# MotorSheet.net
KiCad netlist of a schematic drawn in Altium Designer
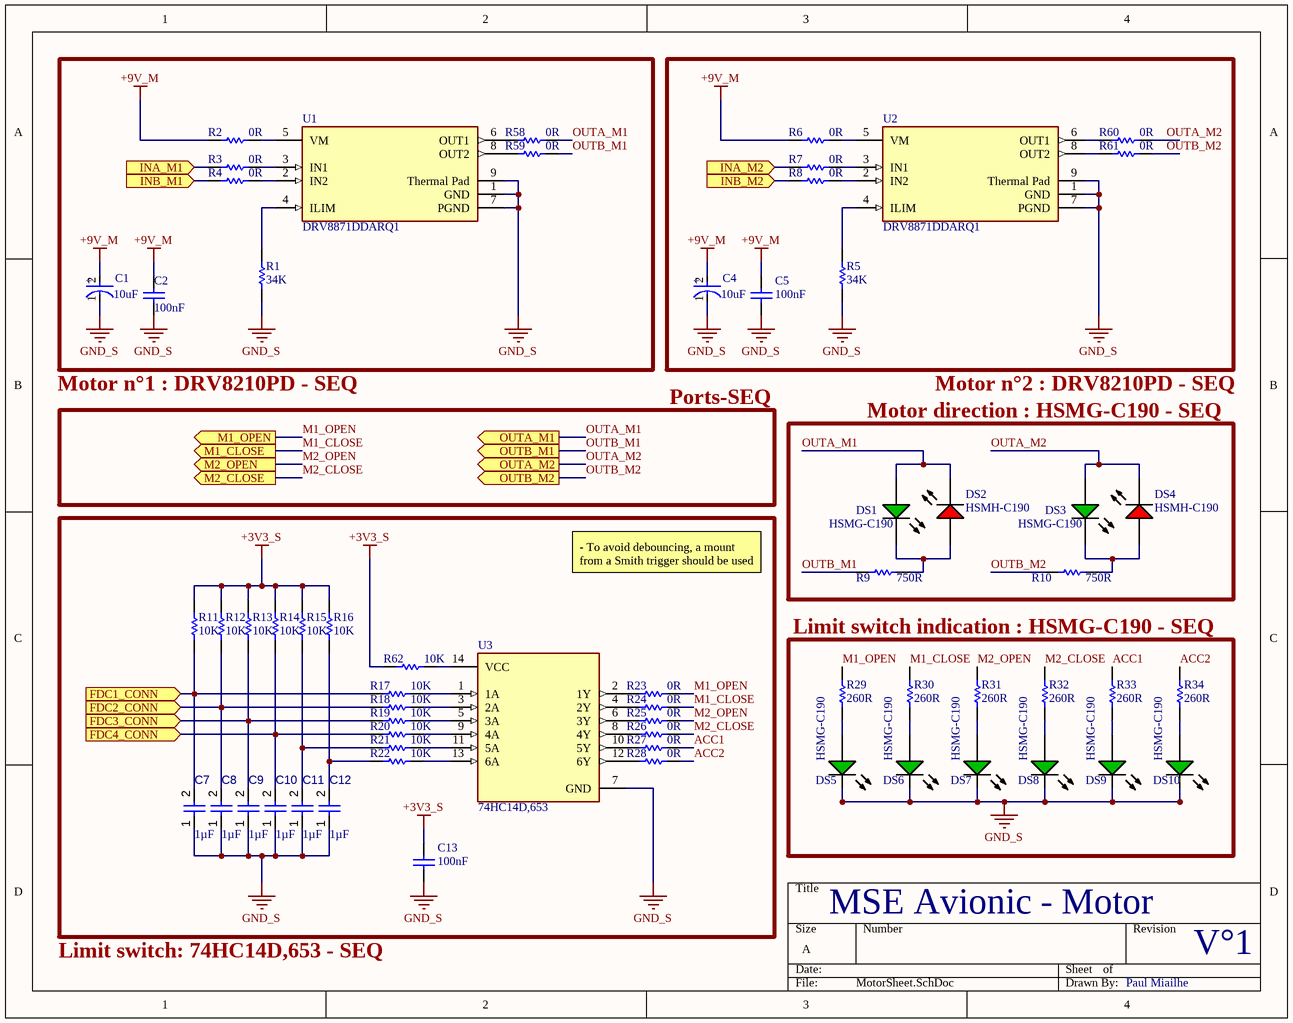
[diagram p0: MotorSheet.SchDoc]

(export (version "E")
  (design (tool "Eeschema 10.0.6"))
  (components
    (comp (ref "C1")
      (value "EEE1VA100SR")
      (footprint "FP-SC-MFG")
      (description "CAP ALUM 10UF 20% 35V SMD")
      (fields
        (field (name "CAPACITANCE") "10uF")
        (field (name "TOLERANCE") "20%")
        (field (name "VOLTAGE") "35V")
      )
      (libsource (lib "Altium Content Vault") (part "203bc49f2ac43e59fd269a8c329ed05"))
    )
    (comp (ref "C2")
      (value "GRM21BR71H104KA01L")
      (footprint "CAPC2013X135X45ML10T25")
      (description "Chip Capacitor, 0.1 uF, +/- 10%, 50 V, -55 to 125 degC, 0805 (2012 Metric), RoHS, Tape and Reel")
      (fields
        (field (name "VOLTAGE") "50V")
        (field (name "CAPACITANCE") "100nF")
        (field (name "TOLERANCE") "10%")
      )
      (libsource (lib "Altium Content Vault") (part "CAP-NP-2"))
    )
    (comp (ref "C4")
      (value "EEE1VA100SR")
      (footprint "FP-SC-MFG")
      (description "CAP ALUM 10UF 20% 35V SMD")
      (fields
        (field (name "CAPACITANCE") "10uF")
        (field (name "TOLERANCE") "20%")
        (field (name "VOLTAGE") "35V")
      )
      (libsource (lib "Altium Content Vault") (part "203bc49f2ac43e59fd269a8c329ed05"))
    )
    (comp (ref "C5")
      (value "GRM21BR71H104KA01L")
      (footprint "CAPC2013X135X45ML10T25")
      (description "Chip Capacitor, 0.1 uF, +/- 10%, 50 V, -55 to 125 degC, 0805 (2012 Metric), RoHS, Tape and Reel")
      (fields
        (field (name "VOLTAGE") "50V")
        (field (name "CAPACITANCE") "100nF")
        (field (name "TOLERANCE") "10%")
      )
      (libsource (lib "Altium Content Vault") (part "CAP-NP-2"))
    )
    (comp (ref "C7")
      (value "1µF")
      (footprint "CAPC0603(1608)100_L")
      (description "Chip Capacitor, 1µF +/-0.1%, 25V, 0603, Thickness 1 mm")
      (fields (field (name "TOLERANCE") "20%") (field (name "Comment") "Capacitor 1µF +/-0.1% 25V 0603"))
      (libsource (lib "Saint-Étienne School of Mines- Mines Space") (part "CAP-NP-2"))
    )
    (comp (ref "C8")
      (value "1µF")
      (footprint "CAPC0603(1608)100_L")
      (description "Chip Capacitor, 1µF +/-0.1%, 25V, 0603, Thickness 1 mm")
      (fields (field (name "TOLERANCE") "20%") (field (name "Comment") "Capacitor 1µF +/-0.1% 25V 0603"))
      (libsource (lib "Saint-Étienne School of Mines- Mines Space") (part "CAP-NP-2"))
    )
    (comp (ref "C9")
      (value "1µF")
      (footprint "CAPC0603(1608)100_L")
      (description "Chip Capacitor, 1µF +/-0.1%, 25V, 0603, Thickness 1 mm")
      (fields (field (name "TOLERANCE") "20%") (field (name "Comment") "Capacitor 1µF +/-0.1% 25V 0603"))
      (libsource (lib "Saint-Étienne School of Mines- Mines Space") (part "CAP-NP-2"))
    )
    (comp (ref "C10")
      (value "1µF")
      (footprint "CAPC0603(1608)100_L")
      (description "Chip Capacitor, 1µF +/-0.1%, 25V, 0603, Thickness 1 mm")
      (fields (field (name "TOLERANCE") "20%") (field (name "Comment") "Capacitor 1µF +/-0.1% 25V 0603"))
      (libsource (lib "Saint-Étienne School of Mines- Mines Space") (part "CAP-NP-2"))
    )
    (comp (ref "C11")
      (value "1µF")
      (footprint "CAPC0603(1608)100_L")
      (description "Chip Capacitor, 1µF +/-0.1%, 25V, 0603, Thickness 1 mm")
      (fields (field (name "TOLERANCE") "20%") (field (name "Comment") "Capacitor 1µF +/-0.1% 25V 0603"))
      (libsource (lib "Saint-Étienne School of Mines- Mines Space") (part "CAP-NP-2"))
    )
    (comp (ref "C12")
      (value "1µF")
      (footprint "CAPC0603(1608)100_L")
      (description "Chip Capacitor, 1µF +/-0.1%, 25V, 0603, Thickness 1 mm")
      (fields (field (name "TOLERANCE") "20%") (field (name "Comment") "Capacitor 1µF +/-0.1% 25V 0603"))
      (libsource (lib "Saint-Étienne School of Mines- Mines Space") (part "CAP-NP-2"))
    )
    (comp (ref "C13")
      (value "GRM21BR71H104KA01L")
      (footprint "CAPC2013X135X45ML10T25")
      (description "Chip Capacitor, 0.1 uF, +/- 10%, 50 V, -55 to 125 degC, 0805 (2012 Metric), RoHS, Tape and Reel")
      (fields
        (field (name "VOLTAGE") "50V")
        (field (name "CAPACITANCE") "100nF")
        (field (name "TOLERANCE") "10%")
      )
      (libsource (lib "Altium Content Vault") (part "CAP-NP-2"))
    )
    (comp (ref "DS1")
      (value "HSMG-C190")
      (footprint "AVAG-HSMX-C190_V")
      (description "Chip LED, Green, 2.2 V, -40 to 85 degC, 2-Pin SMD, RoHS, Tape and Reel")
      (libsource (lib "Altium Content Vault") (part "LED-GREEN-AK-2"))
    )
    (comp (ref "DS2")
      (value "HSMH-C190")
      (footprint "AVAG-HSMX-C190_V")
      (description "LED Uni-Color Red, 65 mW, 20 mA, -40 to 85 degC, 2-Pin SMD, RoHS, Tape and Reel")
      (libsource (lib "Altium Content Vault") (part "LED-RED-AK-2"))
    )
    (comp (ref "DS3")
      (value "HSMG-C190")
      (footprint "AVAG-HSMX-C190_V")
      (description "Chip LED, Green, 2.2 V, -40 to 85 degC, 2-Pin SMD, RoHS, Tape and Reel")
      (libsource (lib "Altium Content Vault") (part "LED-GREEN-AK-2"))
    )
    (comp (ref "DS4")
      (value "HSMH-C190")
      (footprint "AVAG-HSMX-C190_V")
      (description "LED Uni-Color Red, 65 mW, 20 mA, -40 to 85 degC, 2-Pin SMD, RoHS, Tape and Reel")
      (libsource (lib "Altium Content Vault") (part "LED-RED-AK-2"))
    )
    (comp (ref "DS5")
      (value "HSMG-C190")
      (footprint "AVAG-HSMX-C190_V")
      (description "Chip LED, Green, 2.2 V, -40 to 85 degC, 2-Pin SMD, RoHS, Tape and Reel")
      (libsource (lib "Altium Content Vault") (part "LED-GREEN-AK-2"))
    )
    (comp (ref "DS6")
      (value "HSMG-C190")
      (footprint "AVAG-HSMX-C190_V")
      (description "Chip LED, Green, 2.2 V, -40 to 85 degC, 2-Pin SMD, RoHS, Tape and Reel")
      (libsource (lib "Altium Content Vault") (part "LED-GREEN-AK-2"))
    )
    (comp (ref "DS7")
      (value "HSMG-C190")
      (footprint "AVAG-HSMX-C190_V")
      (description "Chip LED, Green, 2.2 V, -40 to 85 degC, 2-Pin SMD, RoHS, Tape and Reel")
      (libsource (lib "Altium Content Vault") (part "LED-GREEN-AK-2"))
    )
    (comp (ref "DS8")
      (value "HSMG-C190")
      (footprint "AVAG-HSMX-C190_V")
      (description "Chip LED, Green, 2.2 V, -40 to 85 degC, 2-Pin SMD, RoHS, Tape and Reel")
      (libsource (lib "Altium Content Vault") (part "LED-GREEN-AK-2"))
    )
    (comp (ref "DS9")
      (value "HSMG-C190")
      (footprint "AVAG-HSMX-C190_V")
      (description "Chip LED, Green, 2.2 V, -40 to 85 degC, 2-Pin SMD, RoHS, Tape and Reel")
      (libsource (lib "Altium Content Vault") (part "LED-GREEN-AK-2"))
    )
    (comp (ref "DS10")
      (value "HSMG-C190")
      (footprint "AVAG-HSMX-C190_V")
      (description "Chip LED, Green, 2.2 V, -40 to 85 degC, 2-Pin SMD, RoHS, Tape and Reel")
      (libsource (lib "Altium Content Vault") (part "LED-GREEN-AK-2"))
    )
    (comp (ref "R1")
      (value "RC0603JR-070RL")
      (footprint "RESC1608X55X25ML10T15")
      (description "Chip Resistor, 0 Ohm, +/- 5%, 0.1 W, -55 to 155 degC, 0603 (1608 Metric), RoHS, Tape and Reel")
      (fields
        (field (name "TOLERANCE") "5%")
        (field (name "RESISTANCE") "34K")
        (field (name "MANUFACTURER") "Yageo")
      )
      (libsource (lib "Altium Content Vault") (part "RES-2"))
    )
    (comp (ref "R2")
      (value "RC0603JR-070RL")
      (footprint "RESC1608X55X25ML10T15")
      (description "Chip Resistor, 0 Ohm, +/- 5%, 0.1 W, -55 to 155 degC, 0603 (1608 Metric), RoHS, Tape and Reel")
      (fields
        (field (name "TOLERANCE") "5%")
        (field (name "RESISTANCE") "0R")
        (field (name "MANUFACTURER") "Yageo")
      )
      (libsource (lib "Altium Content Vault") (part "RES-2"))
    )
    (comp (ref "R3")
      (value "RC0603JR-070RL")
      (footprint "RESC1608X55X25ML10T15")
      (description "Chip Resistor, 0 Ohm, +/- 5%, 0.1 W, -55 to 155 degC, 0603 (1608 Metric), RoHS, Tape and Reel")
      (fields
        (field (name "TOLERANCE") "5%")
        (field (name "RESISTANCE") "0R")
        (field (name "MANUFACTURER") "Yageo")
      )
      (libsource (lib "Altium Content Vault") (part "RES-2"))
    )
    (comp (ref "R4")
      (value "RC0603JR-070RL")
      (footprint "RESC1608X55X25ML10T15")
      (description "Chip Resistor, 0 Ohm, +/- 5%, 0.1 W, -55 to 155 degC, 0603 (1608 Metric), RoHS, Tape and Reel")
      (fields
        (field (name "TOLERANCE") "5%")
        (field (name "RESISTANCE") "0R")
        (field (name "MANUFACTURER") "Yageo")
      )
      (libsource (lib "Altium Content Vault") (part "RES-2"))
    )
    (comp (ref "R5")
      (value "RC0603JR-070RL")
      (footprint "RESC1608X55X25ML10T15")
      (description "Chip Resistor, 0 Ohm, +/- 5%, 0.1 W, -55 to 155 degC, 0603 (1608 Metric), RoHS, Tape and Reel")
      (fields
        (field (name "TOLERANCE") "5%")
        (field (name "RESISTANCE") "34K")
        (field (name "MANUFACTURER") "Yageo")
      )
      (libsource (lib "Altium Content Vault") (part "RES-2"))
    )
    (comp (ref "R6")
      (value "RC0603JR-070RL")
      (footprint "RESC1608X55X25ML10T15")
      (description "Chip Resistor, 0 Ohm, +/- 5%, 0.1 W, -55 to 155 degC, 0603 (1608 Metric), RoHS, Tape and Reel")
      (fields
        (field (name "TOLERANCE") "5%")
        (field (name "RESISTANCE") "0R")
        (field (name "MANUFACTURER") "Yageo")
      )
      (libsource (lib "Altium Content Vault") (part "RES-2"))
    )
    (comp (ref "R7")
      (value "RC0603JR-070RL")
      (footprint "RESC1608X55X25ML10T15")
      (description "Chip Resistor, 0 Ohm, +/- 5%, 0.1 W, -55 to 155 degC, 0603 (1608 Metric), RoHS, Tape and Reel")
      (fields
        (field (name "TOLERANCE") "5%")
        (field (name "RESISTANCE") "0R")
        (field (name "MANUFACTURER") "Yageo")
      )
      (libsource (lib "Altium Content Vault") (part "RES-2"))
    )
    (comp (ref "R8")
      (value "RC0603JR-070RL")
      (footprint "RESC1608X55X25ML10T15")
      (description "Chip Resistor, 0 Ohm, +/- 5%, 0.1 W, -55 to 155 degC, 0603 (1608 Metric), RoHS, Tape and Reel")
      (fields
        (field (name "TOLERANCE") "5%")
        (field (name "RESISTANCE") "0R")
        (field (name "MANUFACTURER") "Yageo")
      )
      (libsource (lib "Altium Content Vault") (part "RES-2"))
    )
    (comp (ref "R9")
      (value "ERA-3AEB751V")
      (footprint "RESC1608X55X30ML20T20")
      (fields
        (field (name "MANUFACTURER") "Panasonic")
        (field (name "TOLERANCE") "0.1%")
        (field (name "RESISTANCE") "750R")
      )
      (libsource (lib "Altium Content Vault") (part "RES"))
    )
    (comp (ref "R10")
      (value "ERA-3AEB751V")
      (footprint "RESC1608X55X30ML20T20")
      (fields
        (field (name "MANUFACTURER") "Panasonic")
        (field (name "TOLERANCE") "0.1%")
        (field (name "RESISTANCE") "750R")
      )
      (libsource (lib "Altium Content Vault") (part "RES"))
    )
    (comp (ref "R11")
      (value "ERJ3EKF1002V")
      (footprint "RESC1609X55X30LL15T15")
      (description "Chip Resistor, 10 KOhm, +/- 1%, 0.1 W, -55 to 155 degC, 0603 (1608 Metric), RoHS, Tape and Reel")
      (fields
        (field (name "RESISTANCE") "10K")
        (field (name "TOLERANCE") "1%")
        (field (name "MANUFACTURER") "Panasonic")
      )
      (libsource (lib "Altium Content Vault") (part "RES-2"))
    )
    (comp (ref "R12")
      (value "ERJ3EKF1002V")
      (footprint "RESC1609X55X30LL15T15")
      (description "Chip Resistor, 10 KOhm, +/- 1%, 0.1 W, -55 to 155 degC, 0603 (1608 Metric), RoHS, Tape and Reel")
      (fields
        (field (name "RESISTANCE") "10K")
        (field (name "TOLERANCE") "1%")
        (field (name "MANUFACTURER") "Panasonic")
      )
      (libsource (lib "Altium Content Vault") (part "RES-2"))
    )
    (comp (ref "R13")
      (value "ERJ3EKF1002V")
      (footprint "RESC1609X55X30LL15T15")
      (description "Chip Resistor, 10 KOhm, +/- 1%, 0.1 W, -55 to 155 degC, 0603 (1608 Metric), RoHS, Tape and Reel")
      (fields
        (field (name "RESISTANCE") "10K")
        (field (name "TOLERANCE") "1%")
        (field (name "MANUFACTURER") "Panasonic")
      )
      (libsource (lib "Altium Content Vault") (part "RES-2"))
    )
    (comp (ref "R14")
      (value "ERJ3EKF1002V")
      (footprint "RESC1609X55X30LL15T15")
      (description "Chip Resistor, 10 KOhm, +/- 1%, 0.1 W, -55 to 155 degC, 0603 (1608 Metric), RoHS, Tape and Reel")
      (fields
        (field (name "RESISTANCE") "10K")
        (field (name "TOLERANCE") "1%")
        (field (name "MANUFACTURER") "Panasonic")
      )
      (libsource (lib "Altium Content Vault") (part "RES-2"))
    )
    (comp (ref "R15")
      (value "ERJ3EKF1002V")
      (footprint "RESC1609X55X30LL15T15")
      (description "Chip Resistor, 10 KOhm, +/- 1%, 0.1 W, -55 to 155 degC, 0603 (1608 Metric), RoHS, Tape and Reel")
      (fields
        (field (name "RESISTANCE") "10K")
        (field (name "TOLERANCE") "1%")
        (field (name "MANUFACTURER") "Panasonic")
      )
      (libsource (lib "Altium Content Vault") (part "RES-2"))
    )
    (comp (ref "R16")
      (value "ERJ3EKF1002V")
      (footprint "RESC1609X55X30LL15T15")
      (description "Chip Resistor, 10 KOhm, +/- 1%, 0.1 W, -55 to 155 degC, 0603 (1608 Metric), RoHS, Tape and Reel")
      (fields
        (field (name "RESISTANCE") "10K")
        (field (name "TOLERANCE") "1%")
        (field (name "MANUFACTURER") "Panasonic")
      )
      (libsource (lib "Altium Content Vault") (part "RES-2"))
    )
    (comp (ref "R17")
      (value "ERJ3EKF1002V")
      (footprint "RESC1609X55X30LL15T15")
      (description "Chip Resistor, 10 KOhm, +/- 1%, 0.1 W, -55 to 155 degC, 0603 (1608 Metric), RoHS, Tape and Reel")
      (fields
        (field (name "RESISTANCE") "10K")
        (field (name "TOLERANCE") "1%")
        (field (name "MANUFACTURER") "Panasonic")
      )
      (libsource (lib "Altium Content Vault") (part "RES-2"))
    )
    (comp (ref "R18")
      (value "ERJ3EKF1002V")
      (footprint "RESC1609X55X30LL15T15")
      (description "Chip Resistor, 10 KOhm, +/- 1%, 0.1 W, -55 to 155 degC, 0603 (1608 Metric), RoHS, Tape and Reel")
      (fields
        (field (name "RESISTANCE") "10K")
        (field (name "TOLERANCE") "1%")
        (field (name "MANUFACTURER") "Panasonic")
      )
      (libsource (lib "Altium Content Vault") (part "RES-2"))
    )
    (comp (ref "R19")
      (value "ERJ3EKF1002V")
      (footprint "RESC1609X55X30LL15T15")
      (description "Chip Resistor, 10 KOhm, +/- 1%, 0.1 W, -55 to 155 degC, 0603 (1608 Metric), RoHS, Tape and Reel")
      (fields
        (field (name "RESISTANCE") "10K")
        (field (name "TOLERANCE") "1%")
        (field (name "MANUFACTURER") "Panasonic")
      )
      (libsource (lib "Altium Content Vault") (part "RES-2"))
    )
    (comp (ref "R20")
      (value "ERJ3EKF1002V")
      (footprint "RESC1609X55X30LL15T15")
      (description "Chip Resistor, 10 KOhm, +/- 1%, 0.1 W, -55 to 155 degC, 0603 (1608 Metric), RoHS, Tape and Reel")
      (fields
        (field (name "RESISTANCE") "10K")
        (field (name "TOLERANCE") "1%")
        (field (name "MANUFACTURER") "Panasonic")
      )
      (libsource (lib "Altium Content Vault") (part "RES-2"))
    )
    (comp (ref "R21")
      (value "ERJ3EKF1002V")
      (footprint "RESC1609X55X30LL15T15")
      (description "Chip Resistor, 10 KOhm, +/- 1%, 0.1 W, -55 to 155 degC, 0603 (1608 Metric), RoHS, Tape and Reel")
      (fields
        (field (name "RESISTANCE") "10K")
        (field (name "TOLERANCE") "1%")
        (field (name "MANUFACTURER") "Panasonic")
      )
      (libsource (lib "Altium Content Vault") (part "RES-2"))
    )
    (comp (ref "R22")
      (value "ERJ3EKF1002V")
      (footprint "RESC1609X55X30LL15T15")
      (description "Chip Resistor, 10 KOhm, +/- 1%, 0.1 W, -55 to 155 degC, 0603 (1608 Metric), RoHS, Tape and Reel")
      (fields
        (field (name "RESISTANCE") "10K")
        (field (name "TOLERANCE") "1%")
        (field (name "MANUFACTURER") "Panasonic")
      )
      (libsource (lib "Altium Content Vault") (part "RES-2"))
    )
    (comp (ref "R23")
      (value "RC0603JR-070RL")
      (footprint "RESC1608X55X25ML10T15")
      (description "Chip Resistor, 0 Ohm, +/- 5%, 0.1 W, -55 to 155 degC, 0603 (1608 Metric), RoHS, Tape and Reel")
      (fields
        (field (name "TOLERANCE") "5%")
        (field (name "RESISTANCE") "0R")
        (field (name "MANUFACTURER") "Yageo")
      )
      (libsource (lib "Altium Content Vault") (part "RES-2"))
    )
    (comp (ref "R24")
      (value "RC0603JR-070RL")
      (footprint "RESC1608X55X25ML10T15")
      (description "Chip Resistor, 0 Ohm, +/- 5%, 0.1 W, -55 to 155 degC, 0603 (1608 Metric), RoHS, Tape and Reel")
      (fields
        (field (name "TOLERANCE") "5%")
        (field (name "RESISTANCE") "0R")
        (field (name "MANUFACTURER") "Yageo")
      )
      (libsource (lib "Altium Content Vault") (part "RES-2"))
    )
    (comp (ref "R25")
      (value "RC0603JR-070RL")
      (footprint "RESC1608X55X25ML10T15")
      (description "Chip Resistor, 0 Ohm, +/- 5%, 0.1 W, -55 to 155 degC, 0603 (1608 Metric), RoHS, Tape and Reel")
      (fields
        (field (name "TOLERANCE") "5%")
        (field (name "RESISTANCE") "0R")
        (field (name "MANUFACTURER") "Yageo")
      )
      (libsource (lib "Altium Content Vault") (part "RES-2"))
    )
    (comp (ref "R26")
      (value "RC0603JR-070RL")
      (footprint "RESC1608X55X25ML10T15")
      (description "Chip Resistor, 0 Ohm, +/- 5%, 0.1 W, -55 to 155 degC, 0603 (1608 Metric), RoHS, Tape and Reel")
      (fields
        (field (name "TOLERANCE") "5%")
        (field (name "RESISTANCE") "0R")
        (field (name "MANUFACTURER") "Yageo")
      )
      (libsource (lib "Altium Content Vault") (part "RES-2"))
    )
    (comp (ref "R27")
      (value "RC0603JR-070RL")
      (footprint "RESC1608X55X25ML10T15")
      (description "Chip Resistor, 0 Ohm, +/- 5%, 0.1 W, -55 to 155 degC, 0603 (1608 Metric), RoHS, Tape and Reel")
      (fields
        (field (name "TOLERANCE") "5%")
        (field (name "RESISTANCE") "0R")
        (field (name "MANUFACTURER") "Yageo")
      )
      (libsource (lib "Altium Content Vault") (part "RES-2"))
    )
    (comp (ref "R28")
      (value "RC0603JR-070RL")
      (footprint "RESC1608X55X25ML10T15")
      (description "Chip Resistor, 0 Ohm, +/- 5%, 0.1 W, -55 to 155 degC, 0603 (1608 Metric), RoHS, Tape and Reel")
      (fields
        (field (name "TOLERANCE") "5%")
        (field (name "RESISTANCE") "0R")
        (field (name "MANUFACTURER") "Yageo")
      )
      (libsource (lib "Altium Content Vault") (part "RES-2"))
    )
    (comp (ref "R29")
      (value "260R")
      (footprint "RESC1609X50X30NL8T20")
      (fields (field (name "MANUFACTURER") "Vishay Semiconductor"))
      (libsource (lib "Altium Content Vault") (part "RES-2"))
    )
    (comp (ref "R30")
      (value "260R")
      (footprint "RESC1609X50X30NL8T20")
      (fields (field (name "MANUFACTURER") "Vishay Semiconductor"))
      (libsource (lib "Altium Content Vault") (part "RES-2"))
    )
    (comp (ref "R31")
      (value "260R")
      (footprint "RESC1609X50X30NL8T20")
      (fields (field (name "MANUFACTURER") "Vishay Semiconductor"))
      (libsource (lib "Altium Content Vault") (part "RES-2"))
    )
    (comp (ref "R32")
      (value "260R")
      (footprint "RESC1609X50X30NL8T20")
      (fields (field (name "MANUFACTURER") "Vishay Semiconductor"))
      (libsource (lib "Altium Content Vault") (part "RES-2"))
    )
    (comp (ref "R33")
      (value "260R")
      (footprint "RESC1609X50X30NL8T20")
      (fields (field (name "MANUFACTURER") "Vishay Semiconductor"))
      (libsource (lib "Altium Content Vault") (part "RES-2"))
    )
    (comp (ref "R34")
      (value "260R")
      (footprint "RESC1609X50X30NL8T20")
      (fields (field (name "MANUFACTURER") "Vishay Semiconductor"))
      (libsource (lib "Altium Content Vault") (part "RES-2"))
    )
    (comp (ref "R58")
      (value "RC0603JR-070RL")
      (footprint "RESC1608X55X25ML10T15")
      (description "Chip Resistor, 0 Ohm, +/- 5%, 0.1 W, -55 to 155 degC, 0603 (1608 Metric), RoHS, Tape and Reel")
      (fields
        (field (name "TOLERANCE") "5%")
        (field (name "RESISTANCE") "0R")
        (field (name "MANUFACTURER") "Yageo")
      )
      (libsource (lib "Altium Content Vault") (part "RES-2"))
    )
    (comp (ref "R59")
      (value "RC0603JR-070RL")
      (footprint "RESC1608X55X25ML10T15")
      (description "Chip Resistor, 0 Ohm, +/- 5%, 0.1 W, -55 to 155 degC, 0603 (1608 Metric), RoHS, Tape and Reel")
      (fields
        (field (name "TOLERANCE") "5%")
        (field (name "RESISTANCE") "0R")
        (field (name "MANUFACTURER") "Yageo")
      )
      (libsource (lib "Altium Content Vault") (part "RES-2"))
    )
    (comp (ref "R60")
      (value "RC0603JR-070RL")
      (footprint "RESC1608X55X25ML10T15")
      (description "Chip Resistor, 0 Ohm, +/- 5%, 0.1 W, -55 to 155 degC, 0603 (1608 Metric), RoHS, Tape and Reel")
      (fields
        (field (name "TOLERANCE") "5%")
        (field (name "RESISTANCE") "0R")
        (field (name "MANUFACTURER") "Yageo")
      )
      (libsource (lib "Altium Content Vault") (part "RES-2"))
    )
    (comp (ref "R61")
      (value "RC0603JR-070RL")
      (footprint "RESC1608X55X25ML10T15")
      (description "Chip Resistor, 0 Ohm, +/- 5%, 0.1 W, -55 to 155 degC, 0603 (1608 Metric), RoHS, Tape and Reel")
      (fields
        (field (name "TOLERANCE") "5%")
        (field (name "RESISTANCE") "0R")
        (field (name "MANUFACTURER") "Yageo")
      )
      (libsource (lib "Altium Content Vault") (part "RES-2"))
    )
    (comp (ref "R62")
      (value "ERJ3EKF1002V")
      (footprint "RESC1609X55X30LL15T15")
      (description "Chip Resistor, 10 KOhm, +/- 1%, 0.1 W, -55 to 155 degC, 0603 (1608 Metric), RoHS, Tape and Reel")
      (fields
        (field (name "RESISTANCE") "10K")
        (field (name "TOLERANCE") "1%")
        (field (name "MANUFACTURER") "Panasonic")
      )
      (libsource (lib "Altium Content Vault") (part "RES-2"))
    )
    (comp (ref "U1")
      (value "DRV8871DDARQ1")
      (footprint "FP-DDA0008E-IPC_A")
      (description "IC MOTOR DRVR UNIPLR 8SO PWRPAD")
      (libsource (lib "Altium Content Vault") (part "1a9033cc3838abb65a985570a4ce709"))
    )
    (comp (ref "U2")
      (value "DRV8871DDARQ1")
      (footprint "FP-DDA0008E-IPC_A")
      (description "IC MOTOR DRVR UNIPLR 8SO PWRPAD")
      (libsource (lib "Altium Content Vault") (part "1a9033cc3838abb65a985570a4ce709"))
    )
    (comp (ref "U3")
      (value "74HC14D,653")
      (footprint "FP-SOT108-1-MFG")
      (description "IC INVERTER SCHMITT 6CH 14SO")
      (libsource (lib "Altium Content Vault") (part "daebd495c2cbd071528ddf4a03b206b"))
    )
  )
  (nets
    (net (code "1") (name "+3V3_S") (class "Default")
      (node (ref "C13") (pin "2") (pinfunction "2_2") (pintype "passive"))
      (node (ref "R11") (pin "2") (pinfunction "2_2") (pintype "passive"))
      (node (ref "R12") (pin "2") (pinfunction "2_2") (pintype "passive"))
      (node (ref "R13") (pin "2") (pinfunction "2_2") (pintype "passive"))
      (node (ref "R14") (pin "2") (pinfunction "2_2") (pintype "passive"))
      (node (ref "R15") (pin "2") (pinfunction "2_2") (pintype "passive"))
      (node (ref "R16") (pin "2") (pinfunction "2_2") (pintype "passive"))
      (node (ref "R62") (pin "2") (pinfunction "2_2") (pintype "passive"))
    )
    (net (code "2") (name "+9V_M") (class "Default")
      (node (ref "C1") (pin "2") (pinfunction "A_2") (pintype "passive"))
      (node (ref "C2") (pin "2") (pinfunction "2_2") (pintype "passive"))
      (node (ref "C4") (pin "2") (pinfunction "A_2") (pintype "passive"))
      (node (ref "C5") (pin "2") (pinfunction "2_2") (pintype "passive"))
      (node (ref "R2") (pin "1") (pinfunction "1_1") (pintype "passive"))
      (node (ref "R6") (pin "1") (pinfunction "1_1") (pintype "passive"))
    )
    (net (code "3") (name "/ACC1") (class "Default")
      (node (ref "R27") (pin "2") (pinfunction "2_2") (pintype "passive"))
      (node (ref "R33") (pin "1") (pinfunction "1_1") (pintype "passive"))
    )
    (net (code "4") (name "/ACC2") (class "Default")
      (node (ref "R28") (pin "2") (pinfunction "2_2") (pintype "passive"))
      (node (ref "R34") (pin "1") (pinfunction "1_1") (pintype "passive"))
    )
    (net (code "5") (name "/FDC1_CONN") (class "Default")
      (node (ref "C7") (pin "2") (pinfunction "2_2") (pintype "passive"))
      (node (ref "R11") (pin "1") (pinfunction "1_1") (pintype "passive"))
      (node (ref "R17") (pin "2") (pinfunction "2_2") (pintype "passive"))
    )
    (net (code "6") (name "/FDC2_CONN") (class "Default")
      (node (ref "C8") (pin "2") (pinfunction "2_2") (pintype "passive"))
      (node (ref "R12") (pin "1") (pinfunction "1_1") (pintype "passive"))
      (node (ref "R18") (pin "2") (pinfunction "2_2") (pintype "passive"))
    )
    (net (code "7") (name "/FDC3_CONN") (class "Default")
      (node (ref "C9") (pin "2") (pinfunction "2_2") (pintype "passive"))
      (node (ref "R13") (pin "1") (pinfunction "1_1") (pintype "passive"))
      (node (ref "R19") (pin "2") (pinfunction "2_2") (pintype "passive"))
    )
    (net (code "8") (name "/FDC4_CONN") (class "Default")
      (node (ref "C10") (pin "2") (pinfunction "2_2") (pintype "passive"))
      (node (ref "R14") (pin "1") (pinfunction "1_1") (pintype "passive"))
      (node (ref "R20") (pin "2") (pinfunction "2_2") (pintype "passive"))
    )
    (net (code "9") (name "/INA_M1") (class "Default")
      (node (ref "R3") (pin "1") (pinfunction "1_1") (pintype "passive"))
    )
    (net (code "10") (name "/INA_M2") (class "Default")
      (node (ref "R7") (pin "1") (pinfunction "1_1") (pintype "passive"))
    )
    (net (code "11") (name "/INB_M1") (class "Default")
      (node (ref "R4") (pin "1") (pinfunction "1_1") (pintype "passive"))
    )
    (net (code "12") (name "/INB_M2") (class "Default")
      (node (ref "R8") (pin "1") (pinfunction "1_1") (pintype "passive"))
    )
    (net (code "13") (name "/M1_CLOSE") (class "Default")
      (node (ref "R24") (pin "2") (pinfunction "2_2") (pintype "passive"))
      (node (ref "R30") (pin "1") (pinfunction "1_1") (pintype "passive"))
    )
    (net (code "14") (name "/M1_OPEN") (class "Default")
      (node (ref "R23") (pin "2") (pinfunction "2_2") (pintype "passive"))
      (node (ref "R29") (pin "1") (pinfunction "1_1") (pintype "passive"))
    )
    (net (code "15") (name "/M2_CLOSE") (class "Default")
      (node (ref "R26") (pin "2") (pinfunction "2_2") (pintype "passive"))
      (node (ref "R32") (pin "1") (pinfunction "1_1") (pintype "passive"))
    )
    (net (code "16") (name "/M2_OPEN") (class "Default")
      (node (ref "R25") (pin "2") (pinfunction "2_2") (pintype "passive"))
      (node (ref "R31") (pin "1") (pinfunction "1_1") (pintype "passive"))
    )
    (net (code "17") (name "/OUTA_M1") (class "Default")
      (node (ref "DS1") (pin "1") (pinfunction "A_1") (pintype "passive"))
      (node (ref "DS2") (pin "2") (pinfunction "K_2") (pintype "passive"))
      (node (ref "R58") (pin "2") (pinfunction "2_2") (pintype "passive"))
    )
    (net (code "18") (name "/OUTA_M2") (class "Default")
      (node (ref "DS3") (pin "1") (pinfunction "A_1") (pintype "passive"))
      (node (ref "DS4") (pin "2") (pinfunction "K_2") (pintype "passive"))
      (node (ref "R60") (pin "2") (pinfunction "2_2") (pintype "passive"))
    )
    (net (code "19") (name "/OUTB_M1") (class "Default")
      (node (ref "R59") (pin "2") (pinfunction "2_2") (pintype "passive"))
      (node (ref "R9") (pin "1") (pinfunction "1_1") (pintype "passive"))
    )
    (net (code "20") (name "/OUTB_M2") (class "Default")
      (node (ref "R10") (pin "1") (pinfunction "1_1") (pintype "passive"))
      (node (ref "R61") (pin "2") (pinfunction "2_2") (pintype "passive"))
    )
    (net (code "21") (name "GND_S") (class "Default")
      (node (ref "C1") (pin "1") (pinfunction "C_1") (pintype "passive"))
      (node (ref "C10") (pin "1") (pinfunction "1_1") (pintype "passive"))
      (node (ref "C11") (pin "1") (pinfunction "1_1") (pintype "passive"))
      (node (ref "C12") (pin "1") (pinfunction "1_1") (pintype "passive"))
      (node (ref "C13") (pin "1") (pinfunction "1_1") (pintype "passive"))
      (node (ref "C2") (pin "1") (pinfunction "1_1") (pintype "passive"))
      (node (ref "C4") (pin "1") (pinfunction "C_1") (pintype "passive"))
      (node (ref "C5") (pin "1") (pinfunction "1_1") (pintype "passive"))
      (node (ref "C7") (pin "1") (pinfunction "1_1") (pintype "passive"))
      (node (ref "C8") (pin "1") (pinfunction "1_1") (pintype "passive"))
      (node (ref "C9") (pin "1") (pinfunction "1_1") (pintype "passive"))
      (node (ref "DS10") (pin "2") (pinfunction "K_2") (pintype "passive"))
      (node (ref "DS5") (pin "2") (pinfunction "K_2") (pintype "passive"))
      (node (ref "DS6") (pin "2") (pinfunction "K_2") (pintype "passive"))
      (node (ref "DS7") (pin "2") (pinfunction "K_2") (pintype "passive"))
      (node (ref "DS8") (pin "2") (pinfunction "K_2") (pintype "passive"))
      (node (ref "DS9") (pin "2") (pinfunction "K_2") (pintype "passive"))
      (node (ref "R1") (pin "1") (pinfunction "1_1") (pintype "passive"))
      (node (ref "R5") (pin "1") (pinfunction "1_1") (pintype "passive"))
      (node (ref "U1") (pin "1") (pinfunction "GND_1") (pintype "power_in"))
      (node (ref "U1") (pin "7") (pinfunction "PGND_7") (pintype "power_in"))
      (node (ref "U1") (pin "9") (pinfunction "Thermal_Pad_9") (pintype "passive"))
      (node (ref "U2") (pin "1") (pinfunction "GND_1") (pintype "power_in"))
      (node (ref "U2") (pin "7") (pinfunction "PGND_7") (pintype "power_in"))
      (node (ref "U2") (pin "9") (pinfunction "Thermal_Pad_9") (pintype "passive"))
      (node (ref "U3") (pin "7") (pinfunction "GND_7") (pintype "power_in"))
    )
    (net (code "22") (name "Net-(C11-Pad2)") (class "Default")
      (node (ref "C11") (pin "2") (pinfunction "2_2") (pintype "passive"))
      (node (ref "R15") (pin "1") (pinfunction "1_1") (pintype "passive"))
      (node (ref "R21") (pin "2") (pinfunction "2_2") (pintype "passive"))
    )
    (net (code "23") (name "Net-(C12-Pad2)") (class "Default")
      (node (ref "C12") (pin "2") (pinfunction "2_2") (pintype "passive"))
      (node (ref "R16") (pin "1") (pinfunction "1_1") (pintype "passive"))
      (node (ref "R22") (pin "2") (pinfunction "2_2") (pintype "passive"))
    )
    (net (code "24") (name "Net-(DS1-K)") (class "Default")
      (node (ref "DS1") (pin "2") (pinfunction "K_2") (pintype "passive"))
      (node (ref "DS2") (pin "1") (pinfunction "A_1") (pintype "passive"))
      (node (ref "R9") (pin "2") (pinfunction "2_2") (pintype "passive"))
    )
    (net (code "25") (name "Net-(DS3-K)") (class "Default")
      (node (ref "DS3") (pin "2") (pinfunction "K_2") (pintype "passive"))
      (node (ref "DS4") (pin "1") (pinfunction "A_1") (pintype "passive"))
      (node (ref "R10") (pin "2") (pinfunction "2_2") (pintype "passive"))
    )
    (net (code "26") (name "Net-(DS5-A)") (class "Default")
      (node (ref "DS5") (pin "1") (pinfunction "A_1") (pintype "passive"))
      (node (ref "R29") (pin "2") (pinfunction "2_2") (pintype "passive"))
    )
    (net (code "27") (name "Net-(DS6-A)") (class "Default")
      (node (ref "DS6") (pin "1") (pinfunction "A_1") (pintype "passive"))
      (node (ref "R30") (pin "2") (pinfunction "2_2") (pintype "passive"))
    )
    (net (code "28") (name "Net-(DS7-A)") (class "Default")
      (node (ref "DS7") (pin "1") (pinfunction "A_1") (pintype "passive"))
      (node (ref "R31") (pin "2") (pinfunction "2_2") (pintype "passive"))
    )
    (net (code "29") (name "Net-(DS8-A)") (class "Default")
      (node (ref "DS8") (pin "1") (pinfunction "A_1") (pintype "passive"))
      (node (ref "R32") (pin "2") (pinfunction "2_2") (pintype "passive"))
    )
    (net (code "30") (name "Net-(DS9-A)") (class "Default")
      (node (ref "DS9") (pin "1") (pinfunction "A_1") (pintype "passive"))
      (node (ref "R33") (pin "2") (pinfunction "2_2") (pintype "passive"))
    )
    (net (code "31") (name "Net-(DS10-A)") (class "Default")
      (node (ref "DS10") (pin "1") (pinfunction "A_1") (pintype "passive"))
      (node (ref "R34") (pin "2") (pinfunction "2_2") (pintype "passive"))
    )
    (net (code "32") (name "Net-(U1-ILIM)") (class "Default")
      (node (ref "R1") (pin "2") (pinfunction "2_2") (pintype "passive"))
      (node (ref "U1") (pin "4") (pinfunction "ILIM_4") (pintype "input"))
    )
    (net (code "33") (name "Net-(U1-IN1)") (class "Default")
      (node (ref "R3") (pin "2") (pinfunction "2_2") (pintype "passive"))
      (node (ref "U1") (pin "3") (pinfunction "IN1_3") (pintype "input"))
    )
    (net (code "34") (name "Net-(U1-IN2)") (class "Default")
      (node (ref "R4") (pin "2") (pinfunction "2_2") (pintype "passive"))
      (node (ref "U1") (pin "2") (pinfunction "IN2_2") (pintype "input"))
    )
    (net (code "35") (name "Net-(U1-OUT1)") (class "Default")
      (node (ref "R58") (pin "1") (pinfunction "1_1") (pintype "passive"))
      (node (ref "U1") (pin "6") (pinfunction "OUT1_6") (pintype "output"))
    )
    (net (code "36") (name "Net-(U1-OUT2)") (class "Default")
      (node (ref "R59") (pin "1") (pinfunction "1_1") (pintype "passive"))
      (node (ref "U1") (pin "8") (pinfunction "OUT2_8") (pintype "output"))
    )
    (net (code "37") (name "Net-(U1-VM)") (class "Default")
      (node (ref "R2") (pin "2") (pinfunction "2_2") (pintype "passive"))
      (node (ref "U1") (pin "5") (pinfunction "VM_5") (pintype "power_in"))
    )
    (net (code "38") (name "Net-(U2-ILIM)") (class "Default")
      (node (ref "R5") (pin "2") (pinfunction "2_2") (pintype "passive"))
      (node (ref "U2") (pin "4") (pinfunction "ILIM_4") (pintype "input"))
    )
    (net (code "39") (name "Net-(U2-IN1)") (class "Default")
      (node (ref "R7") (pin "2") (pinfunction "2_2") (pintype "passive"))
      (node (ref "U2") (pin "3") (pinfunction "IN1_3") (pintype "input"))
    )
    (net (code "40") (name "Net-(U2-IN2)") (class "Default")
      (node (ref "R8") (pin "2") (pinfunction "2_2") (pintype "passive"))
      (node (ref "U2") (pin "2") (pinfunction "IN2_2") (pintype "input"))
    )
    (net (code "41") (name "Net-(U2-OUT1)") (class "Default")
      (node (ref "R60") (pin "1") (pinfunction "1_1") (pintype "passive"))
      (node (ref "U2") (pin "6") (pinfunction "OUT1_6") (pintype "output"))
    )
    (net (code "42") (name "Net-(U2-OUT2)") (class "Default")
      (node (ref "R61") (pin "1") (pinfunction "1_1") (pintype "passive"))
      (node (ref "U2") (pin "8") (pinfunction "OUT2_8") (pintype "output"))
    )
    (net (code "43") (name "Net-(U2-VM)") (class "Default")
      (node (ref "R6") (pin "2") (pinfunction "2_2") (pintype "passive"))
      (node (ref "U2") (pin "5") (pinfunction "VM_5") (pintype "power_in"))
    )
    (net (code "44") (name "Net-(U3-1A)") (class "Default")
      (node (ref "R17") (pin "1") (pinfunction "1_1") (pintype "passive"))
      (node (ref "U3") (pin "1") (pinfunction "1A_1") (pintype "input"))
    )
    (net (code "45") (name "Net-(U3-1Y)") (class "Default")
      (node (ref "R23") (pin "1") (pinfunction "1_1") (pintype "passive"))
      (node (ref "U3") (pin "2") (pinfunction "1Y_2") (pintype "output"))
    )
    (net (code "46") (name "Net-(U3-2A)") (class "Default")
      (node (ref "R18") (pin "1") (pinfunction "1_1") (pintype "passive"))
      (node (ref "U3") (pin "3") (pinfunction "2A_3") (pintype "input"))
    )
    (net (code "47") (name "Net-(U3-2Y)") (class "Default")
      (node (ref "R24") (pin "1") (pinfunction "1_1") (pintype "passive"))
      (node (ref "U3") (pin "4") (pinfunction "2Y_4") (pintype "output"))
    )
    (net (code "48") (name "Net-(U3-3A)") (class "Default")
      (node (ref "R19") (pin "1") (pinfunction "1_1") (pintype "passive"))
      (node (ref "U3") (pin "5") (pinfunction "3A_5") (pintype "input"))
    )
    (net (code "49") (name "Net-(U3-3Y)") (class "Default")
      (node (ref "R25") (pin "1") (pinfunction "1_1") (pintype "passive"))
      (node (ref "U3") (pin "6") (pinfunction "3Y_6") (pintype "output"))
    )
    (net (code "50") (name "Net-(U3-4A)") (class "Default")
      (node (ref "R20") (pin "1") (pinfunction "1_1") (pintype "passive"))
      (node (ref "U3") (pin "9") (pinfunction "4A_9") (pintype "input"))
    )
    (net (code "51") (name "Net-(U3-4Y)") (class "Default")
      (node (ref "R26") (pin "1") (pinfunction "1_1") (pintype "passive"))
      (node (ref "U3") (pin "8") (pinfunction "4Y_8") (pintype "output"))
    )
    (net (code "52") (name "Net-(U3-5A)") (class "Default")
      (node (ref "R21") (pin "1") (pinfunction "1_1") (pintype "passive"))
      (node (ref "U3") (pin "11") (pinfunction "5A_11") (pintype "input"))
    )
    (net (code "53") (name "Net-(U3-5Y)") (class "Default")
      (node (ref "R27") (pin "1") (pinfunction "1_1") (pintype "passive"))
      (node (ref "U3") (pin "10") (pinfunction "5Y_10") (pintype "output"))
    )
    (net (code "54") (name "Net-(U3-6A)") (class "Default")
      (node (ref "R22") (pin "1") (pinfunction "1_1") (pintype "passive"))
      (node (ref "U3") (pin "13") (pinfunction "6A_13") (pintype "input"))
    )
    (net (code "55") (name "Net-(U3-6Y)") (class "Default")
      (node (ref "R28") (pin "1") (pinfunction "1_1") (pintype "passive"))
      (node (ref "U3") (pin "12") (pinfunction "6Y_12") (pintype "output"))
    )
    (net (code "56") (name "Net-(U3-VCC)") (class "Default")
      (node (ref "R62") (pin "1") (pinfunction "1_1") (pintype "passive"))
      (node (ref "U3") (pin "14") (pinfunction "VCC_14") (pintype "power_in"))
    )
  )
)
